# Shield.net
KiCad netlist of a schematic drawn in EAGLE
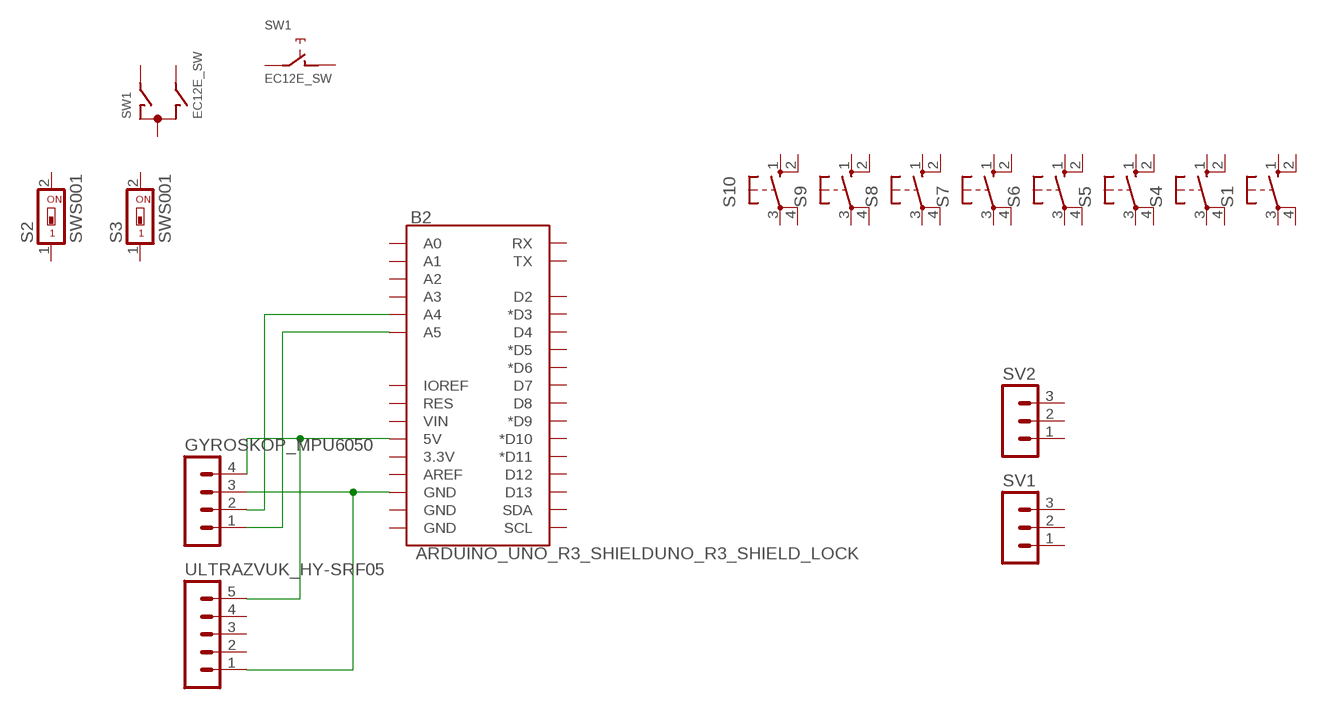
[diagram p0: schematic, sheet 1]

(export (version "E")
  (design (tool "Eeschema 10.0.6"))
  (components
    (comp (ref "B2")
      (value "ARDUINO_UNO_R3_SHIELDUNO_R3_SHIELD_LOCK")
      (footprint "eagle-import:UNO_R3_SHIELD_LOCK")
      (libsource (lib "eagle-import") (part "ARDUINO_UNO_R3_SHIELDUNO_R3_SHIELD_LOCK"))
    )
    (comp (ref "GYROSKOP_MPU6050")
      (value "MA04-1")
      (footprint "eagle-import:MA04-1")
      (libsource (lib "eagle-import") (part "MA04-1"))
    )
    (comp (ref "S1")
      (value "10-XX")
      (footprint "eagle-import:B3F-10XX")
      (fields (field (name "MPN") "B3F-1000"))
      (libsource (lib "eagle-import") (part "10-XX"))
    )
    (comp (ref "S2")
      (value "SWS001")
      (footprint "eagle-import:SMS-001")
      (libsource (lib "eagle-import") (part "SWS001"))
    )
    (comp (ref "S3")
      (value "SWS001")
      (footprint "eagle-import:SMS-001")
      (libsource (lib "eagle-import") (part "SWS001"))
    )
    (comp (ref "S4")
      (value "10-XX")
      (footprint "eagle-import:B3F-10XX")
      (fields (field (name "MPN") "B3F-1000"))
      (libsource (lib "eagle-import") (part "10-XX"))
    )
    (comp (ref "S5")
      (value "10-XX")
      (footprint "eagle-import:B3F-10XX")
      (fields (field (name "MPN") "B3F-1000"))
      (libsource (lib "eagle-import") (part "10-XX"))
    )
    (comp (ref "S6")
      (value "10-XX")
      (footprint "eagle-import:B3F-10XX")
      (fields (field (name "MPN") "B3F-1000"))
      (libsource (lib "eagle-import") (part "10-XX"))
    )
    (comp (ref "S7")
      (value "10-XX")
      (footprint "eagle-import:B3F-10XX")
      (fields (field (name "MPN") "B3F-1000"))
      (libsource (lib "eagle-import") (part "10-XX"))
    )
    (comp (ref "S8")
      (value "10-XX")
      (footprint "eagle-import:B3F-10XX")
      (fields (field (name "MPN") "B3F-1000"))
      (libsource (lib "eagle-import") (part "10-XX"))
    )
    (comp (ref "S9")
      (value "10-XX")
      (footprint "eagle-import:B3F-10XX")
      (fields (field (name "MPN") "B3F-1000"))
      (libsource (lib "eagle-import") (part "10-XX"))
    )
    (comp (ref "S10")
      (value "10-XX")
      (footprint "eagle-import:B3F-10XX")
      (fields (field (name "MPN") "B3F-1000"))
      (libsource (lib "eagle-import") (part "10-XX"))
    )
    (comp (ref "SV1")
      (value "MA03-1")
      (footprint "eagle-import:MA03-1")
      (libsource (lib "eagle-import") (part "MA03-1"))
    )
    (comp (ref "SV2")
      (value "MA03-1")
      (footprint "eagle-import:MA03-1")
      (libsource (lib "eagle-import") (part "MA03-1"))
    )
    (comp (ref "SW1")
      (value "EC12E_SW")
      (footprint "eagle-import:ALPS_EC12E_SW")
      (fields (field (name "MPN") "EC12E2424407"))
      (libsource (lib "eagle-import") (part "EC12E_SW"))
    )
    (comp (ref "ULTRAZVUK_HY-SRF05")
      (value "MA05-1")
      (footprint "eagle-import:MA05-1")
      (libsource (lib "eagle-import") (part "MA05-1"))
    )
  )
  (nets
    (net (code "1") (name "Net-(B2-GND-PadGND@2)") (class "Default")
      (node (ref "B2") (pin "GND@2") (pinfunction "GND_GND@2") (pintype "bidirectional"))
      (node (ref "GYROSKOP_MPU6050") (pin "3") (pinfunction "3_3") (pintype "passive"))
      (node (ref "ULTRAZVUK_HY-SRF05") (pin "1") (pinfunction "1_1") (pintype "passive"))
    )
    (net (code "2") (name "Net-(B2-Pad5V)") (class "Default")
      (node (ref "B2") (pin "5V") (pinfunction "5V_5V") (pintype "bidirectional"))
      (node (ref "GYROSKOP_MPU6050") (pin "4") (pinfunction "4_4") (pintype "passive"))
      (node (ref "ULTRAZVUK_HY-SRF05") (pin "5") (pinfunction "5_5") (pintype "passive"))
    )
    (net (code "3") (name "Net-(B2-PadA4)") (class "Default")
      (node (ref "B2") (pin "A4") (pinfunction "A4_A4") (pintype "bidirectional"))
      (node (ref "GYROSKOP_MPU6050") (pin "2") (pinfunction "2_2") (pintype "passive"))
    )
    (net (code "4") (name "Net-(B2-PadA5)") (class "Default")
      (node (ref "B2") (pin "A5") (pinfunction "A5_A5") (pintype "bidirectional"))
      (node (ref "GYROSKOP_MPU6050") (pin "1") (pinfunction "1_1") (pintype "passive"))
    )
    (net (code "5") (name "unconnected-(B2-*D3-PadD3)") (class "Default")
      (node (ref "B2") (pin "D3") (pinfunction "*D3_D3") (pintype "bidirectional"))
    )
    (net (code "6") (name "unconnected-(B2-*D5-PadD5)") (class "Default")
      (node (ref "B2") (pin "D5") (pinfunction "*D5_D5") (pintype "bidirectional"))
    )
    (net (code "7") (name "unconnected-(B2-*D6-PadD6)") (class "Default")
      (node (ref "B2") (pin "D6") (pinfunction "*D6_D6") (pintype "bidirectional"))
    )
    (net (code "8") (name "unconnected-(B2-*D9-PadD9)") (class "Default")
      (node (ref "B2") (pin "D9") (pinfunction "*D9_D9") (pintype "bidirectional"))
    )
    (net (code "9") (name "unconnected-(B2-*D10-PadD10)") (class "Default")
      (node (ref "B2") (pin "D10") (pinfunction "*D10_D10") (pintype "bidirectional"))
    )
    (net (code "10") (name "unconnected-(B2-*D11-PadD11)") (class "Default")
      (node (ref "B2") (pin "D11") (pinfunction "*D11_D11") (pintype "bidirectional"))
    )
    (net (code "11") (name "unconnected-(B2-GND-PadGND@0)") (class "Default")
      (node (ref "B2") (pin "GND@0") (pinfunction "GND_GND@0") (pintype "bidirectional"))
    )
    (net (code "12") (name "unconnected-(B2-GND-PadGND@1)") (class "Default")
      (node (ref "B2") (pin "GND@1") (pinfunction "GND_GND@1") (pintype "bidirectional"))
    )
    (net (code "13") (name "unconnected-(B2-Pad3.3V)") (class "Default")
      (node (ref "B2") (pin "3.3V") (pinfunction "3.3V_3.3V") (pintype "bidirectional"))
    )
    (net (code "14") (name "unconnected-(B2-PadA0)") (class "Default")
      (node (ref "B2") (pin "A0") (pinfunction "A0_A0") (pintype "bidirectional"))
    )
    (net (code "15") (name "unconnected-(B2-PadA1)") (class "Default")
      (node (ref "B2") (pin "A1") (pinfunction "A1_A1") (pintype "bidirectional"))
    )
    (net (code "16") (name "unconnected-(B2-PadA2)") (class "Default")
      (node (ref "B2") (pin "A2") (pinfunction "A2_A2") (pintype "bidirectional"))
    )
    (net (code "17") (name "unconnected-(B2-PadA3)") (class "Default")
      (node (ref "B2") (pin "A3") (pinfunction "A3_A3") (pintype "bidirectional"))
    )
    (net (code "18") (name "unconnected-(B2-PadAREF)") (class "Default")
      (node (ref "B2") (pin "AREF") (pinfunction "AREF_AREF") (pintype "bidirectional"))
    )
    (net (code "19") (name "unconnected-(B2-PadD2)") (class "Default")
      (node (ref "B2") (pin "D2") (pinfunction "D2_D2") (pintype "bidirectional"))
    )
    (net (code "20") (name "unconnected-(B2-PadD4)") (class "Default")
      (node (ref "B2") (pin "D4") (pinfunction "D4_D4") (pintype "bidirectional"))
    )
    (net (code "21") (name "unconnected-(B2-PadD7)") (class "Default")
      (node (ref "B2") (pin "D7") (pinfunction "D7_D7") (pintype "bidirectional"))
    )
    (net (code "22") (name "unconnected-(B2-PadD8)") (class "Default")
      (node (ref "B2") (pin "D8") (pinfunction "D8_D8") (pintype "bidirectional"))
    )
    (net (code "23") (name "unconnected-(B2-PadD12)") (class "Default")
      (node (ref "B2") (pin "D12") (pinfunction "D12_D12") (pintype "bidirectional"))
    )
    (net (code "24") (name "unconnected-(B2-PadD13)") (class "Default")
      (node (ref "B2") (pin "D13") (pinfunction "D13_D13") (pintype "bidirectional"))
    )
    (net (code "25") (name "unconnected-(B2-PadIOREF)") (class "Default")
      (node (ref "B2") (pin "IOREF") (pinfunction "IOREF_IOREF") (pintype "bidirectional"))
    )
    (net (code "26") (name "unconnected-(B2-PadRES)") (class "Default")
      (node (ref "B2") (pin "RES") (pinfunction "RES_RES") (pintype "bidirectional"))
    )
    (net (code "27") (name "unconnected-(B2-PadRX)") (class "Default")
      (node (ref "B2") (pin "RX") (pinfunction "RX_RX") (pintype "bidirectional"))
    )
    (net (code "28") (name "unconnected-(B2-PadSCL)") (class "Default")
      (node (ref "B2") (pin "SCL") (pinfunction "SCL_SCL") (pintype "bidirectional"))
    )
    (net (code "29") (name "unconnected-(B2-PadSDA)") (class "Default")
      (node (ref "B2") (pin "SDA") (pinfunction "SDA_SDA") (pintype "bidirectional"))
    )
    (net (code "30") (name "unconnected-(B2-PadTX)") (class "Default")
      (node (ref "B2") (pin "TX") (pinfunction "TX_TX") (pintype "bidirectional"))
    )
    (net (code "31") (name "unconnected-(B2-PadVIN)") (class "Default")
      (node (ref "B2") (pin "VIN") (pinfunction "VIN_VIN") (pintype "bidirectional"))
    )
    (net (code "32") (name "unconnected-(S1-P-Pad3)") (class "Default")
      (node (ref "S1") (pin "3") (pinfunction "P_3") (pintype "passive"))
    )
    (net (code "33") (name "unconnected-(S1-P1-Pad4)") (class "Default")
      (node (ref "S1") (pin "4") (pinfunction "P1_4") (pintype "passive"))
    )
    (net (code "34") (name "unconnected-(S1-S-Pad1)") (class "Default")
      (node (ref "S1") (pin "1") (pinfunction "S_1") (pintype "passive"))
    )
    (net (code "35") (name "unconnected-(S1-S1-Pad2)") (class "Default")
      (node (ref "S1") (pin "2") (pinfunction "S1_2") (pintype "passive"))
    )
    (net (code "36") (name "unconnected-(S2-Pad1)") (class "Default")
      (node (ref "S2") (pin "1") (pinfunction "1_1") (pintype "passive"))
    )
    (net (code "37") (name "unconnected-(S2-Pad2)") (class "Default")
      (node (ref "S2") (pin "2") (pinfunction "2_2") (pintype "passive"))
    )
    (net (code "38") (name "unconnected-(S3-Pad1)") (class "Default")
      (node (ref "S3") (pin "1") (pinfunction "1_1") (pintype "passive"))
    )
    (net (code "39") (name "unconnected-(S3-Pad2)") (class "Default")
      (node (ref "S3") (pin "2") (pinfunction "2_2") (pintype "passive"))
    )
    (net (code "40") (name "unconnected-(S4-P-Pad3)") (class "Default")
      (node (ref "S4") (pin "3") (pinfunction "P_3") (pintype "passive"))
    )
    (net (code "41") (name "unconnected-(S4-P1-Pad4)") (class "Default")
      (node (ref "S4") (pin "4") (pinfunction "P1_4") (pintype "passive"))
    )
    (net (code "42") (name "unconnected-(S4-S-Pad1)") (class "Default")
      (node (ref "S4") (pin "1") (pinfunction "S_1") (pintype "passive"))
    )
    (net (code "43") (name "unconnected-(S4-S1-Pad2)") (class "Default")
      (node (ref "S4") (pin "2") (pinfunction "S1_2") (pintype "passive"))
    )
    (net (code "44") (name "unconnected-(S5-P-Pad3)") (class "Default")
      (node (ref "S5") (pin "3") (pinfunction "P_3") (pintype "passive"))
    )
    (net (code "45") (name "unconnected-(S5-P1-Pad4)") (class "Default")
      (node (ref "S5") (pin "4") (pinfunction "P1_4") (pintype "passive"))
    )
    (net (code "46") (name "unconnected-(S5-S-Pad1)") (class "Default")
      (node (ref "S5") (pin "1") (pinfunction "S_1") (pintype "passive"))
    )
    (net (code "47") (name "unconnected-(S5-S1-Pad2)") (class "Default")
      (node (ref "S5") (pin "2") (pinfunction "S1_2") (pintype "passive"))
    )
    (net (code "48") (name "unconnected-(S6-P-Pad3)") (class "Default")
      (node (ref "S6") (pin "3") (pinfunction "P_3") (pintype "passive"))
    )
    (net (code "49") (name "unconnected-(S6-P1-Pad4)") (class "Default")
      (node (ref "S6") (pin "4") (pinfunction "P1_4") (pintype "passive"))
    )
    (net (code "50") (name "unconnected-(S6-S-Pad1)") (class "Default")
      (node (ref "S6") (pin "1") (pinfunction "S_1") (pintype "passive"))
    )
    (net (code "51") (name "unconnected-(S6-S1-Pad2)") (class "Default")
      (node (ref "S6") (pin "2") (pinfunction "S1_2") (pintype "passive"))
    )
    (net (code "52") (name "unconnected-(S7-P-Pad3)") (class "Default")
      (node (ref "S7") (pin "3") (pinfunction "P_3") (pintype "passive"))
    )
    (net (code "53") (name "unconnected-(S7-P1-Pad4)") (class "Default")
      (node (ref "S7") (pin "4") (pinfunction "P1_4") (pintype "passive"))
    )
    (net (code "54") (name "unconnected-(S7-S-Pad1)") (class "Default")
      (node (ref "S7") (pin "1") (pinfunction "S_1") (pintype "passive"))
    )
    (net (code "55") (name "unconnected-(S7-S1-Pad2)") (class "Default")
      (node (ref "S7") (pin "2") (pinfunction "S1_2") (pintype "passive"))
    )
    (net (code "56") (name "unconnected-(S8-P-Pad3)") (class "Default")
      (node (ref "S8") (pin "3") (pinfunction "P_3") (pintype "passive"))
    )
    (net (code "57") (name "unconnected-(S8-P1-Pad4)") (class "Default")
      (node (ref "S8") (pin "4") (pinfunction "P1_4") (pintype "passive"))
    )
    (net (code "58") (name "unconnected-(S8-S-Pad1)") (class "Default")
      (node (ref "S8") (pin "1") (pinfunction "S_1") (pintype "passive"))
    )
    (net (code "59") (name "unconnected-(S8-S1-Pad2)") (class "Default")
      (node (ref "S8") (pin "2") (pinfunction "S1_2") (pintype "passive"))
    )
    (net (code "60") (name "unconnected-(S9-P-Pad3)") (class "Default")
      (node (ref "S9") (pin "3") (pinfunction "P_3") (pintype "passive"))
    )
    (net (code "61") (name "unconnected-(S9-P1-Pad4)") (class "Default")
      (node (ref "S9") (pin "4") (pinfunction "P1_4") (pintype "passive"))
    )
    (net (code "62") (name "unconnected-(S9-S-Pad1)") (class "Default")
      (node (ref "S9") (pin "1") (pinfunction "S_1") (pintype "passive"))
    )
    (net (code "63") (name "unconnected-(S9-S1-Pad2)") (class "Default")
      (node (ref "S9") (pin "2") (pinfunction "S1_2") (pintype "passive"))
    )
    (net (code "64") (name "unconnected-(S10-P-Pad3)") (class "Default")
      (node (ref "S10") (pin "3") (pinfunction "P_3") (pintype "passive"))
    )
    (net (code "65") (name "unconnected-(S10-P1-Pad4)") (class "Default")
      (node (ref "S10") (pin "4") (pinfunction "P1_4") (pintype "passive"))
    )
    (net (code "66") (name "unconnected-(S10-S-Pad1)") (class "Default")
      (node (ref "S10") (pin "1") (pinfunction "S_1") (pintype "passive"))
    )
    (net (code "67") (name "unconnected-(S10-S1-Pad2)") (class "Default")
      (node (ref "S10") (pin "2") (pinfunction "S1_2") (pintype "passive"))
    )
    (net (code "68") (name "unconnected-(SV1-Pad1)") (class "Default")
      (node (ref "SV1") (pin "1") (pinfunction "1_1") (pintype "passive"))
    )
    (net (code "69") (name "unconnected-(SV1-Pad2)") (class "Default")
      (node (ref "SV1") (pin "2") (pinfunction "2_2") (pintype "passive"))
    )
    (net (code "70") (name "unconnected-(SV1-Pad3)") (class "Default")
      (node (ref "SV1") (pin "3") (pinfunction "3_3") (pintype "passive"))
    )
    (net (code "71") (name "unconnected-(SV2-Pad1)") (class "Default")
      (node (ref "SV2") (pin "1") (pinfunction "1_1") (pintype "passive"))
    )
    (net (code "72") (name "unconnected-(SV2-Pad2)") (class "Default")
      (node (ref "SV2") (pin "2") (pinfunction "2_2") (pintype "passive"))
    )
    (net (code "73") (name "unconnected-(SV2-Pad3)") (class "Default")
      (node (ref "SV2") (pin "3") (pinfunction "3_3") (pintype "passive"))
    )
    (net (code "74") (name "unconnected-(SW1-PadA)") (class "Default")
      (node (ref "SW1") (pin "A") (pinfunction "A_A") (pintype "passive"))
    )
    (net (code "75") (name "unconnected-(SW1-PadB)") (class "Default")
      (node (ref "SW1") (pin "B") (pinfunction "B_B") (pintype "passive"))
    )
    (net (code "76") (name "unconnected-(SW1-PadC)") (class "Default")
      (node (ref "SW1") (pin "C") (pinfunction "C_C") (pintype "passive"))
    )
    (net (code "77") (name "unconnected-(SW1B-1-PadD)") (class "Default")
      (node (ref "SW1") (pin "D") (pinfunction "1_D") (pintype "passive"))
    )
    (net (code "78") (name "unconnected-(SW1B-2-PadE)") (class "Default")
      (node (ref "SW1") (pin "E") (pinfunction "2_E") (pintype "passive"))
    )
    (net (code "79") (name "unconnected-(ULTRAZVUK_HY-SRF05-Pad2)") (class "Default")
      (node (ref "ULTRAZVUK_HY-SRF05") (pin "2") (pinfunction "2_2") (pintype "passive"))
    )
    (net (code "80") (name "unconnected-(ULTRAZVUK_HY-SRF05-Pad3)") (class "Default")
      (node (ref "ULTRAZVUK_HY-SRF05") (pin "3") (pinfunction "3_3") (pintype "passive"))
    )
    (net (code "81") (name "unconnected-(ULTRAZVUK_HY-SRF05-Pad4)") (class "Default")
      (node (ref "ULTRAZVUK_HY-SRF05") (pin "4") (pinfunction "4_4") (pintype "passive"))
    )
  )
)
